# tpa2008d_breakout_board.net
KiCad netlist of a schematic drawn in EAGLE
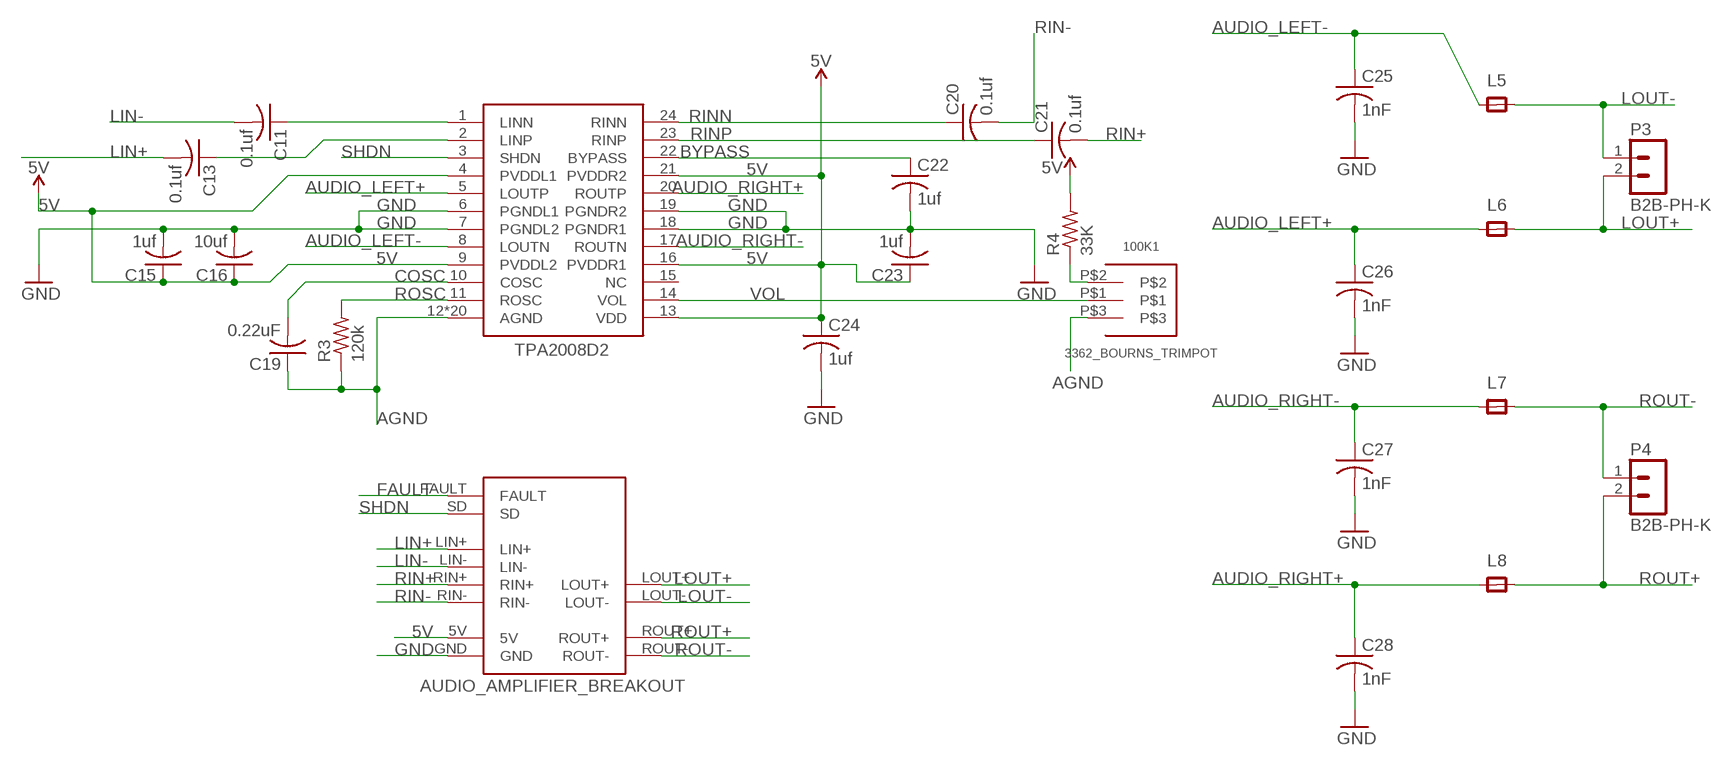
[diagram p0: schematic, sheet 1]

(export (version "E")
  (design (tool "Eeschema 10.0.6"))
  (components
    (comp (ref "100K1")
      (value "3362_BOURNS_TRIMPOT")
      (footprint "eagle-import:3362_BOURNS_TRIMPOT")
      (libsource (lib "eagle-import") (part "3362_BOURNS_TRIMPOT"))
    )
    (comp (ref "C11")
      (value "0.1uf")
      (footprint "eagle-import:C0805")
      (libsource (lib "eagle-import") (part "C-USC0805"))
    )
    (comp (ref "C13")
      (value "0.1uf")
      (footprint "eagle-import:C0805")
      (libsource (lib "eagle-import") (part "C-USC0805"))
    )
    (comp (ref "C15")
      (value "1uf")
      (footprint "eagle-import:C0805")
      (libsource (lib "eagle-import") (part "C-USC0805"))
    )
    (comp (ref "C16")
      (value "10uf")
      (footprint "eagle-import:C0805")
      (libsource (lib "eagle-import") (part "C-USC0805"))
    )
    (comp (ref "C19")
      (value "0.22uF")
      (footprint "eagle-import:C0805")
      (libsource (lib "eagle-import") (part "C-USC0805"))
    )
    (comp (ref "C20")
      (value "0.1uf")
      (footprint "eagle-import:C0805")
      (libsource (lib "eagle-import") (part "C-USC0805"))
    )
    (comp (ref "C21")
      (value "0.1uf")
      (footprint "eagle-import:C0805")
      (libsource (lib "eagle-import") (part "C-USC0805"))
    )
    (comp (ref "C22")
      (value "1uf")
      (footprint "eagle-import:C0805")
      (libsource (lib "eagle-import") (part "C-USC0805"))
    )
    (comp (ref "C23")
      (value "1uf")
      (footprint "eagle-import:C0805")
      (libsource (lib "eagle-import") (part "C-USC0805"))
    )
    (comp (ref "C24")
      (value "1uf")
      (footprint "eagle-import:C0805")
      (libsource (lib "eagle-import") (part "C-USC0805"))
    )
    (comp (ref "C25")
      (value "1nF")
      (footprint "eagle-import:C0805")
      (libsource (lib "eagle-import") (part "C-USC0805"))
    )
    (comp (ref "C26")
      (value "1nF")
      (footprint "eagle-import:C0805")
      (libsource (lib "eagle-import") (part "C-USC0805"))
    )
    (comp (ref "C27")
      (value "1nF")
      (footprint "eagle-import:C0805")
      (libsource (lib "eagle-import") (part "C-USC0805"))
    )
    (comp (ref "C28")
      (value "1nF")
      (footprint "eagle-import:C0805")
      (libsource (lib "eagle-import") (part "C-USC0805"))
    )
    (comp (ref "L5")
      (value "600Ohm@100MHz")
      (footprint "eagle-import:RC-MASTER-SMD_L1206MP")
      (libsource (lib "eagle-import") (part "RC-MASTER-SMD_FB_1206MP"))
    )
    (comp (ref "L6")
      (value "600Ohm@100MHz")
      (footprint "eagle-import:RC-MASTER-SMD_L1206MP")
      (libsource (lib "eagle-import") (part "RC-MASTER-SMD_FB_1206MP"))
    )
    (comp (ref "L7")
      (value "600Ohm@100MHz")
      (footprint "eagle-import:RC-MASTER-SMD_L1206MP")
      (libsource (lib "eagle-import") (part "RC-MASTER-SMD_FB_1206MP"))
    )
    (comp (ref "L8")
      (value "600Ohm@100MHz")
      (footprint "eagle-import:RC-MASTER-SMD_L1206MP")
      (libsource (lib "eagle-import") (part "RC-MASTER-SMD_FB_1206MP"))
    )
    (comp (ref "P3")
      (value "B2B-PH-K")
      (footprint "eagle-import:B2B-PH-K")
      (libsource (lib "eagle-import") (part "B2B-PH-K"))
    )
    (comp (ref "P4")
      (value "B2B-PH-K")
      (footprint "eagle-import:B2B-PH-K")
      (libsource (lib "eagle-import") (part "B2B-PH-K"))
    )
    (comp (ref "R3")
      (value "120k")
      (footprint "eagle-import:M0805")
      (libsource (lib "eagle-import") (part "R-US_M0805"))
    )
    (comp (ref "R4")
      (value "33K")
      (footprint "eagle-import:M0805")
      (libsource (lib "eagle-import") (part "R-US_M0805"))
    )
    (comp (ref "U$2")
      (value "TPA2008D2")
      (footprint "eagle-import:PWP-TSSOP24")
      (libsource (lib "eagle-import") (part "TPA2008D2"))
    )
    (comp (ref "U$3")
      (value "AUDIO_AMPLIFIER_BREAKOUT")
      (footprint "eagle-import:AUDIO_AMPLIFIER_BREAKOUT")
      (libsource (lib "eagle-import") (part "AUDIO_AMPLIFIER_BREAKOUT"))
    )
  )
  (nets
    (net (code "1") (name "/AGND") (class "Default")
      (node (ref "100K1") (pin "P$3") (pinfunction "P$3_P$3") (pintype "bidirectional"))
      (node (ref "C19") (pin "1") (pinfunction "1_1") (pintype "passive"))
      (node (ref "R3") (pin "1") (pinfunction "1_1") (pintype "passive"))
      (node (ref "U$2") (pin "12") (pinfunction "AGND_12") (pintype "bidirectional"))
      (node (ref "U$2") (pin "EXP") (pinfunction "AGND_EXP") (pintype "bidirectional"))
      (node (ref "U$2") (pin "EXP@1") (pinfunction "AGND_EXP@1") (pintype "bidirectional"))
      (node (ref "U$2") (pin "EXP@10") (pinfunction "AGND_EXP@10") (pintype "bidirectional"))
      (node (ref "U$2") (pin "EXP@11") (pinfunction "AGND_EXP@11") (pintype "bidirectional"))
      (node (ref "U$2") (pin "EXP@12") (pinfunction "AGND_EXP@12") (pintype "bidirectional"))
      (node (ref "U$2") (pin "EXP@13") (pinfunction "AGND_EXP@13") (pintype "bidirectional"))
      (node (ref "U$2") (pin "EXP@14") (pinfunction "AGND_EXP@14") (pintype "bidirectional"))
      (node (ref "U$2") (pin "EXP@15") (pinfunction "AGND_EXP@15") (pintype "bidirectional"))
      (node (ref "U$2") (pin "EXP@16") (pinfunction "AGND_EXP@16") (pintype "bidirectional"))
      (node (ref "U$2") (pin "EXP@17") (pinfunction "AGND_EXP@17") (pintype "bidirectional"))
      (node (ref "U$2") (pin "EXP@18") (pinfunction "AGND_EXP@18") (pintype "bidirectional"))
      (node (ref "U$2") (pin "EXP@2") (pinfunction "AGND_EXP@2") (pintype "bidirectional"))
      (node (ref "U$2") (pin "EXP@3") (pinfunction "AGND_EXP@3") (pintype "bidirectional"))
      (node (ref "U$2") (pin "EXP@4") (pinfunction "AGND_EXP@4") (pintype "bidirectional"))
      (node (ref "U$2") (pin "EXP@5") (pinfunction "AGND_EXP@5") (pintype "bidirectional"))
      (node (ref "U$2") (pin "EXP@6") (pinfunction "AGND_EXP@6") (pintype "bidirectional"))
      (node (ref "U$2") (pin "EXP@7") (pinfunction "AGND_EXP@7") (pintype "bidirectional"))
      (node (ref "U$2") (pin "EXP@8") (pinfunction "AGND_EXP@8") (pintype "bidirectional"))
      (node (ref "U$2") (pin "EXP@9") (pinfunction "AGND_EXP@9") (pintype "bidirectional"))
    )
    (net (code "2") (name "/AUDIO_LEFT+") (class "Default")
      (node (ref "C26") (pin "1") (pinfunction "1_1") (pintype "passive"))
      (node (ref "L6") (pin "1") (pinfunction "1_1") (pintype "passive"))
      (node (ref "U$2") (pin "5") (pinfunction "LOUTP_5") (pintype "bidirectional"))
    )
    (net (code "3") (name "/AUDIO_LEFT-") (class "Default")
      (node (ref "C25") (pin "1") (pinfunction "1_1") (pintype "passive"))
      (node (ref "L5") (pin "1") (pinfunction "1_1") (pintype "passive"))
      (node (ref "U$2") (pin "8") (pinfunction "LOUTN_8") (pintype "bidirectional"))
    )
    (net (code "4") (name "/AUDIO_RIGHT+") (class "Default")
      (node (ref "C28") (pin "1") (pinfunction "1_1") (pintype "passive"))
      (node (ref "L8") (pin "1") (pinfunction "1_1") (pintype "passive"))
      (node (ref "U$2") (pin "20") (pinfunction "ROUTP_20") (pintype "bidirectional"))
    )
    (net (code "5") (name "/AUDIO_RIGHT-") (class "Default")
      (node (ref "C27") (pin "1") (pinfunction "1_1") (pintype "passive"))
      (node (ref "L7") (pin "1") (pinfunction "1_1") (pintype "passive"))
      (node (ref "U$2") (pin "17") (pinfunction "ROUTN_17") (pintype "bidirectional"))
    )
    (net (code "6") (name "/BYPASS") (class "Default")
      (node (ref "C22") (pin "1") (pinfunction "1_1") (pintype "passive"))
      (node (ref "U$2") (pin "22") (pinfunction "BYPASS_22") (pintype "bidirectional"))
    )
    (net (code "7") (name "/COSC") (class "Default")
      (node (ref "C19") (pin "2") (pinfunction "2_2") (pintype "passive"))
      (node (ref "U$2") (pin "10") (pinfunction "COSC_10") (pintype "bidirectional"))
    )
    (net (code "8") (name "/FAULT") (class "Default")
      (node (ref "U$3") (pin "FAULT") (pinfunction "FAULT_FAULT") (pintype "bidirectional"))
    )
    (net (code "9") (name "/LIN+") (class "Default")
      (node (ref "C13") (pin "2") (pinfunction "2_2") (pintype "passive"))
      (node (ref "U$3") (pin "LIN+") (pinfunction "LIN+_LIN+") (pintype "bidirectional"))
    )
    (net (code "10") (name "/LIN-") (class "Default")
      (node (ref "C11") (pin "2") (pinfunction "2_2") (pintype "passive"))
      (node (ref "U$3") (pin "LIN-") (pinfunction "LIN-_LIN-") (pintype "bidirectional"))
    )
    (net (code "11") (name "/LOUT+") (class "Default")
      (node (ref "L6") (pin "2") (pinfunction "2_2") (pintype "passive"))
      (node (ref "P3") (pin "2") (pinfunction "2_2") (pintype "passive"))
      (node (ref "U$3") (pin "LOUT+") (pinfunction "LOUT+_LOUT+") (pintype "bidirectional"))
    )
    (net (code "12") (name "/LOUT-") (class "Default")
      (node (ref "L5") (pin "2") (pinfunction "2_2") (pintype "passive"))
      (node (ref "P3") (pin "1") (pinfunction "1_1") (pintype "passive"))
      (node (ref "U$3") (pin "LOUT-") (pinfunction "LOUT-_LOUT-") (pintype "bidirectional"))
    )
    (net (code "13") (name "/RIN+") (class "Default")
      (node (ref "C21") (pin "2") (pinfunction "2_2") (pintype "passive"))
      (node (ref "U$3") (pin "RIN+") (pinfunction "RIN+_RIN+") (pintype "bidirectional"))
    )
    (net (code "14") (name "/RIN-") (class "Default")
      (node (ref "C20") (pin "2") (pinfunction "2_2") (pintype "passive"))
      (node (ref "U$3") (pin "RIN-") (pinfunction "RIN-_RIN-") (pintype "bidirectional"))
    )
    (net (code "15") (name "/RINN") (class "Default")
      (node (ref "C20") (pin "1") (pinfunction "1_1") (pintype "passive"))
      (node (ref "U$2") (pin "24") (pinfunction "RINN_24") (pintype "bidirectional"))
    )
    (net (code "16") (name "/RINP") (class "Default")
      (node (ref "C21") (pin "1") (pinfunction "1_1") (pintype "passive"))
      (node (ref "U$2") (pin "23") (pinfunction "RINP_23") (pintype "bidirectional"))
    )
    (net (code "17") (name "/ROSC") (class "Default")
      (node (ref "R3") (pin "2") (pinfunction "2_2") (pintype "passive"))
      (node (ref "U$2") (pin "11") (pinfunction "ROSC_11") (pintype "bidirectional"))
    )
    (net (code "18") (name "/ROUT+") (class "Default")
      (node (ref "L8") (pin "2") (pinfunction "2_2") (pintype "passive"))
      (node (ref "P4") (pin "2") (pinfunction "2_2") (pintype "passive"))
      (node (ref "U$3") (pin "ROUT+") (pinfunction "ROUT+_ROUT+") (pintype "bidirectional"))
    )
    (net (code "19") (name "/ROUT-") (class "Default")
      (node (ref "L7") (pin "2") (pinfunction "2_2") (pintype "passive"))
      (node (ref "P4") (pin "1") (pinfunction "1_1") (pintype "passive"))
      (node (ref "U$3") (pin "ROUT-") (pinfunction "ROUT-_ROUT-") (pintype "bidirectional"))
    )
    (net (code "20") (name "/SHDN") (class "Default")
      (node (ref "U$2") (pin "3") (pinfunction "SHDN_3") (pintype "bidirectional"))
      (node (ref "U$3") (pin "SD") (pinfunction "SD_SD") (pintype "bidirectional"))
    )
    (net (code "21") (name "/VOL") (class "Default")
      (node (ref "100K1") (pin "P$1") (pinfunction "P$1_P$1") (pintype "bidirectional"))
      (node (ref "U$2") (pin "14") (pinfunction "VOL_14") (pintype "bidirectional"))
    )
    (net (code "22") (name "5V") (class "Default")
      (node (ref "C15") (pin "1") (pinfunction "1_1") (pintype "passive"))
      (node (ref "C16") (pin "1") (pinfunction "1_1") (pintype "passive"))
      (node (ref "C23") (pin "1") (pinfunction "1_1") (pintype "passive"))
      (node (ref "C24") (pin "1") (pinfunction "1_1") (pintype "passive"))
      (node (ref "R4") (pin "2") (pinfunction "2_2") (pintype "passive"))
      (node (ref "U$2") (pin "13") (pinfunction "VDD_13") (pintype "bidirectional"))
      (node (ref "U$2") (pin "16") (pinfunction "PVDDR1_16") (pintype "bidirectional"))
      (node (ref "U$2") (pin "21") (pinfunction "PVDDR2_21") (pintype "bidirectional"))
      (node (ref "U$2") (pin "4") (pinfunction "PVDDL1_4") (pintype "bidirectional"))
      (node (ref "U$2") (pin "9") (pinfunction "PVDDL2_9") (pintype "bidirectional"))
      (node (ref "U$3") (pin "5V") (pinfunction "5V_5V") (pintype "bidirectional"))
    )
    (net (code "23") (name "GND") (class "Default")
      (node (ref "C15") (pin "2") (pinfunction "2_2") (pintype "passive"))
      (node (ref "C16") (pin "2") (pinfunction "2_2") (pintype "passive"))
      (node (ref "C22") (pin "2") (pinfunction "2_2") (pintype "passive"))
      (node (ref "C23") (pin "2") (pinfunction "2_2") (pintype "passive"))
      (node (ref "C24") (pin "2") (pinfunction "2_2") (pintype "passive"))
      (node (ref "C25") (pin "2") (pinfunction "2_2") (pintype "passive"))
      (node (ref "C26") (pin "2") (pinfunction "2_2") (pintype "passive"))
      (node (ref "C27") (pin "2") (pinfunction "2_2") (pintype "passive"))
      (node (ref "C28") (pin "2") (pinfunction "2_2") (pintype "passive"))
      (node (ref "U$2") (pin "18") (pinfunction "PGNDR1_18") (pintype "bidirectional"))
      (node (ref "U$2") (pin "19") (pinfunction "PGNDR2_19") (pintype "bidirectional"))
      (node (ref "U$2") (pin "6") (pinfunction "PGNDL1_6") (pintype "bidirectional"))
      (node (ref "U$2") (pin "7") (pinfunction "PGNDL2_7") (pintype "bidirectional"))
      (node (ref "U$3") (pin "GND") (pinfunction "GND_GND") (pintype "bidirectional"))
    )
    (net (code "24") (name "Net-(100K1-PadP$2)") (class "Default")
      (node (ref "100K1") (pin "P$2") (pinfunction "P$2_P$2") (pintype "bidirectional"))
      (node (ref "R4") (pin "1") (pinfunction "1_1") (pintype "passive"))
    )
    (net (code "25") (name "Net-(U$2-LINN)") (class "Default")
      (node (ref "C11") (pin "1") (pinfunction "1_1") (pintype "passive"))
      (node (ref "U$2") (pin "1") (pinfunction "LINN_1") (pintype "bidirectional"))
    )
    (net (code "26") (name "Net-(U$2-LINP)") (class "Default")
      (node (ref "C13") (pin "1") (pinfunction "1_1") (pintype "passive"))
      (node (ref "U$2") (pin "2") (pinfunction "LINP_2") (pintype "bidirectional"))
    )
    (net (code "27") (name "unconnected-(U$2-NC-Pad15)") (class "Default")
      (node (ref "U$2") (pin "15") (pinfunction "NC_15") (pintype "bidirectional"))
    )
  )
)
